# power_manager_ports.net
KiCad netlist of a schematic drawn in EAGLE
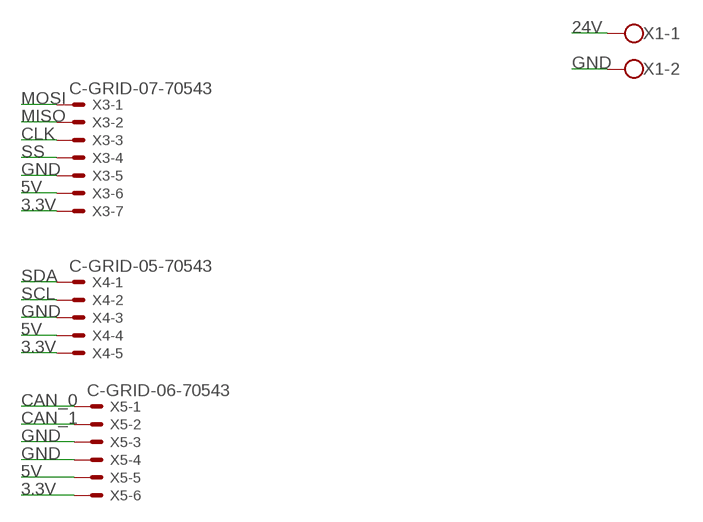
[diagram p0: schematic, sheet 1]

(export (version "E")
  (design (tool "Eeschema 10.0.6"))
  (components
    (comp (ref "X1")
      (value "W239-302")
      (footprint "eagle-import:W239-302")
      (libsource (lib "eagle-import") (part "W239-302"))
    )
    (comp (ref "X3")
      (value "C-GRID-07-70543")
      (footprint "eagle-import:70543-07")
      (fields (field (name "MF") "MOLEX"))
      (libsource (lib "eagle-import") (part "C-GRID-07-70543"))
    )
    (comp (ref "X4")
      (value "C-GRID-05-70543")
      (footprint "eagle-import:70543-05")
      (fields (field (name "MF") "MOLEX"))
      (libsource (lib "eagle-import") (part "C-GRID-05-70543"))
    )
    (comp (ref "X5")
      (value "C-GRID-06-70543")
      (footprint "eagle-import:70543-06")
      (fields (field (name "MF") "MOLEX"))
      (libsource (lib "eagle-import") (part "C-GRID-06-70543"))
    )
  )
  (nets
    (net (code "1") (name "/3.3V") (class "Default")
      (node (ref "X3") (pin "7") (pinfunction "S_7") (pintype "passive"))
      (node (ref "X4") (pin "5") (pinfunction "S_5") (pintype "passive"))
      (node (ref "X5") (pin "6") (pinfunction "S_6") (pintype "passive"))
    )
    (net (code "2") (name "/5V") (class "Default")
      (node (ref "X3") (pin "6") (pinfunction "S_6") (pintype "passive"))
      (node (ref "X4") (pin "4") (pinfunction "S_4") (pintype "passive"))
      (node (ref "X5") (pin "5") (pinfunction "S_5") (pintype "passive"))
    )
    (net (code "3") (name "/24V") (class "Default")
      (node (ref "X1") (pin "1") (pinfunction "KL_1") (pintype "passive"))
    )
    (net (code "4") (name "/CAN_0") (class "Default")
      (node (ref "X5") (pin "1") (pinfunction "S_1") (pintype "passive"))
    )
    (net (code "5") (name "/CAN_1") (class "Default")
      (node (ref "X5") (pin "2") (pinfunction "S_2") (pintype "passive"))
    )
    (net (code "6") (name "/CLK") (class "Default")
      (node (ref "X3") (pin "3") (pinfunction "S_3") (pintype "passive"))
    )
    (net (code "7") (name "/GND") (class "Default")
      (node (ref "X1") (pin "2") (pinfunction "KL_2") (pintype "passive"))
      (node (ref "X3") (pin "5") (pinfunction "S_5") (pintype "passive"))
      (node (ref "X4") (pin "3") (pinfunction "S_3") (pintype "passive"))
      (node (ref "X5") (pin "3") (pinfunction "S_3") (pintype "passive"))
      (node (ref "X5") (pin "4") (pinfunction "S_4") (pintype "passive"))
    )
    (net (code "8") (name "/MISO") (class "Default")
      (node (ref "X3") (pin "2") (pinfunction "S_2") (pintype "passive"))
    )
    (net (code "9") (name "/MOSI") (class "Default")
      (node (ref "X3") (pin "1") (pinfunction "S_1") (pintype "passive"))
    )
    (net (code "10") (name "/SCL") (class "Default")
      (node (ref "X4") (pin "2") (pinfunction "S_2") (pintype "passive"))
    )
    (net (code "11") (name "/SDA") (class "Default")
      (node (ref "X4") (pin "1") (pinfunction "S_1") (pintype "passive"))
    )
    (net (code "12") (name "/SS") (class "Default")
      (node (ref "X3") (pin "4") (pinfunction "S_4") (pintype "passive"))
    )
  )
)
